# Motor_Controllers.net
KiCad netlist of a schematic drawn in Altium Designer
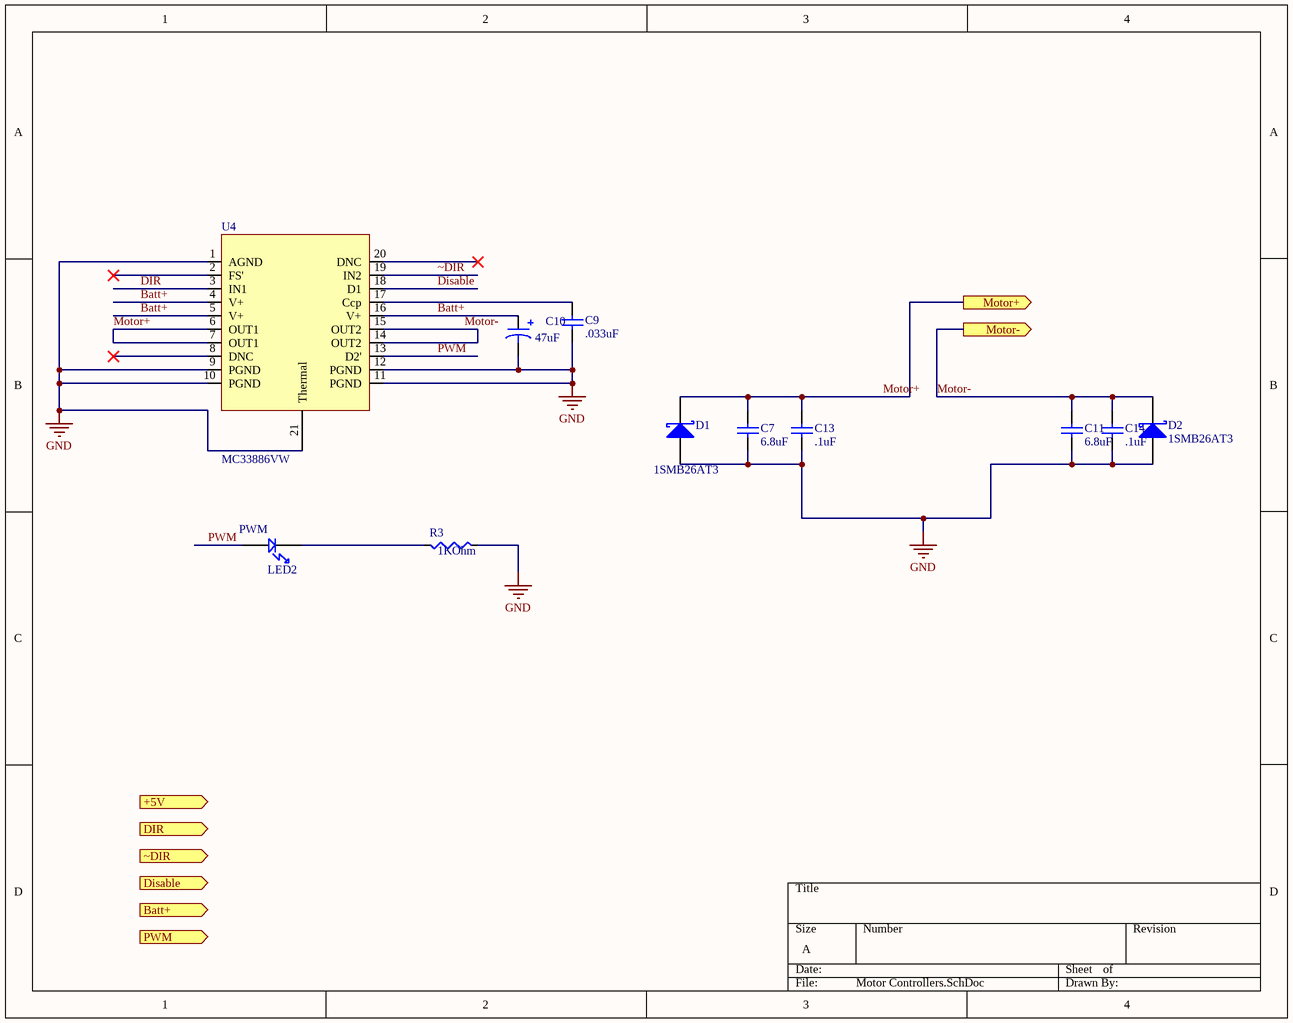
[diagram p0: Motor Controllers.SchDoc]

(export (version "E")
  (design (tool "Eeschema 10.0.6"))
  (components
    (comp (ref "C7")
      (value "6.8uF")
      (footprint "PassiveComponents:1210 (3225) Capacitor")
      (description "Capacitor")
      (libsource (lib "PassiveComponents") (part "Capacitor (non-polarized)"))
    )
    (comp (ref "C9")
      (value ".033uF")
      (footprint "0805 (2012) Capacitor")
      (description "Capacitor")
      (libsource (lib "PassiveComponents") (part "Capacitor (non-polarized)"))
    )
    (comp (ref "C10")
      (value "47uF")
      (footprint "Radial_6.3mmDia_SM_D")
      (description "Capacitor (polarized)")
      (libsource (lib "PassiveComponents") (part "Capacitor (polarized)"))
    )
    (comp (ref "C11")
      (value "6.8uF")
      (footprint "PassiveComponents:1210 (3225) Capacitor")
      (description "Capacitor")
      (libsource (lib "PassiveComponents") (part "Capacitor (non-polarized)"))
    )
    (comp (ref "C13")
      (value ".1uF")
      (footprint "0805 (2012) Capacitor")
      (description "Capacitor")
      (libsource (lib "PassiveComponents") (part "Capacitor (non-polarized)"))
    )
    (comp (ref "C14")
      (value ".1uF")
      (footprint "0805 (2012) Capacitor")
      (description "Capacitor")
      (libsource (lib "PassiveComponents") (part "Capacitor (non-polarized)"))
    )
    (comp (ref "D1")
      (value "1SMB26AT3")
      (footprint "SMB")
      (description "Schottky Diode")
      (fields (field (name "PUBLISHER") "Altium Limited"))
      (libsource (lib "Miscellaneous Devices") (part "D Schottky"))
    )
    (comp (ref "D2")
      (value "1SMB26AT3")
      (footprint "SMB")
      (description "Schottky Diode")
      (fields (field (name "PUBLISHER") "Altium Limited"))
      (libsource (lib "Miscellaneous Devices") (part "D Schottky"))
    )
    (comp (ref "LED2")
      (value "PWM")
      (footprint "LED 0805")
      (description "Standard LED")
      (libsource (lib "PassiveComponents") (part "LED"))
    )
    (comp (ref "R3")
      (value "1KOhm")
      (footprint "R 0805 (2012) RESISTOR")
      (description "Resistor")
      (libsource (lib "PassiveComponents") (part "Resistor"))
    )
    (comp (ref "U4")
      (value "MC33886VW")
      (footprint "SOP127P1420X340_HS-20N")
      (description "Motor Controller")
      (libsource (lib "Kanaloa_v2.0.0_Motor") (part "MC33886VW"))
    )
  )
  (nets
    (net (code "2") (name "/Batt+") (class "Default")
      (node (ref "C10") (pin "P") (pinfunction "1_P") (pintype "passive"))
      (node (ref "U4") (pin "16") (pinfunction "V+_16") (pintype "passive"))
      (node (ref "U4") (pin "4") (pinfunction "V+_4") (pintype "passive"))
      (node (ref "U4") (pin "5") (pinfunction "V+_5") (pintype "passive"))
    )
    (net (code "3") (name "/DIR") (class "Default")
      (node (ref "U4") (pin "3") (pinfunction "IN1_3") (pintype "passive"))
    )
    (net (code "4") (name "/Disable") (class "Default")
      (node (ref "U4") (pin "18") (pinfunction "D1_18") (pintype "passive"))
    )
    (net (code "5") (name "/Motor+") (class "Default")
      (node (ref "C13") (pin "2") (pinfunction "2_2") (pintype "passive"))
      (node (ref "C7") (pin "2") (pinfunction "2_2") (pintype "passive"))
      (node (ref "D1") (pin "2") (pinfunction "K_2") (pintype "passive"))
      (node (ref "U4") (pin "6") (pinfunction "OUT1_6") (pintype "passive"))
      (node (ref "U4") (pin "7") (pinfunction "OUT1_7") (pintype "passive"))
    )
    (net (code "6") (name "/Motor-") (class "Default")
      (node (ref "C11") (pin "2") (pinfunction "2_2") (pintype "passive"))
      (node (ref "C14") (pin "2") (pinfunction "2_2") (pintype "passive"))
      (node (ref "D2") (pin "2") (pinfunction "K_2") (pintype "passive"))
      (node (ref "U4") (pin "14") (pinfunction "OUT2_14") (pintype "passive"))
      (node (ref "U4") (pin "15") (pinfunction "OUT2_15") (pintype "passive"))
    )
    (net (code "7") (name "/PWM") (class "Default")
      (node (ref "LED2") (pin "2") (pinfunction "2_2") (pintype "passive"))
      (node (ref "U4") (pin "13") (pinfunction "D2'_13") (pintype "passive"))
    )
    (net (code "8") (name "/~DIR") (class "Default")
      (node (ref "U4") (pin "19") (pinfunction "IN2_19") (pintype "passive"))
    )
    (net (code "9") (name "GND") (class "Default")
      (node (ref "C10") (pin "N") (pinfunction "2_N") (pintype "passive"))
      (node (ref "C11") (pin "1") (pinfunction "1_1") (pintype "passive"))
      (node (ref "C13") (pin "1") (pinfunction "1_1") (pintype "passive"))
      (node (ref "C14") (pin "1") (pinfunction "1_1") (pintype "passive"))
      (node (ref "C7") (pin "1") (pinfunction "1_1") (pintype "passive"))
      (node (ref "C9") (pin "1") (pinfunction "1_1") (pintype "passive"))
      (node (ref "D1") (pin "1") (pinfunction "A_1") (pintype "passive"))
      (node (ref "D2") (pin "1") (pinfunction "A_1") (pintype "passive"))
      (node (ref "R3") (pin "2") (pinfunction "2_2") (pintype "passive"))
      (node (ref "U4") (pin "1") (pinfunction "AGND_1") (pintype "passive"))
      (node (ref "U4") (pin "10") (pinfunction "PGND_10") (pintype "passive"))
      (node (ref "U4") (pin "11") (pinfunction "PGND_11") (pintype "passive"))
      (node (ref "U4") (pin "12") (pinfunction "PGND_12") (pintype "passive"))
      (node (ref "U4") (pin "21") (pinfunction "Thermal_21") (pintype "passive"))
      (node (ref "U4") (pin "9") (pinfunction "PGND_9") (pintype "passive"))
    )
    (net (code "10") (name "Net-(LED2-Pad1)") (class "Default")
      (node (ref "LED2") (pin "1") (pinfunction "1_1") (pintype "passive"))
      (node (ref "R3") (pin "1") (pinfunction "1_1") (pintype "passive"))
    )
    (net (code "11") (name "Net-(U4-Ccp)") (class "Default")
      (node (ref "C9") (pin "2") (pinfunction "2_2") (pintype "passive"))
      (node (ref "U4") (pin "17") (pinfunction "Ccp_17") (pintype "passive"))
    )
    (net (code "12") (name "unconnected-(U4-DNC-Pad8)") (class "Default")
      (node (ref "U4") (pin "8") (pinfunction "DNC_8") (pintype "passive+no_connect"))
    )
    (net (code "13") (name "unconnected-(U4-DNC-Pad20)") (class "Default")
      (node (ref "U4") (pin "20") (pinfunction "DNC_20") (pintype "passive+no_connect"))
    )
    (net (code "14") (name "unconnected-(U4-FS'-Pad2)") (class "Default")
      (node (ref "U4") (pin "2") (pinfunction "FS'_2") (pintype "passive+no_connect"))
    )
  )
)
